# rpiz_relay.net
KiCad netlist of a schematic drawn in EAGLE
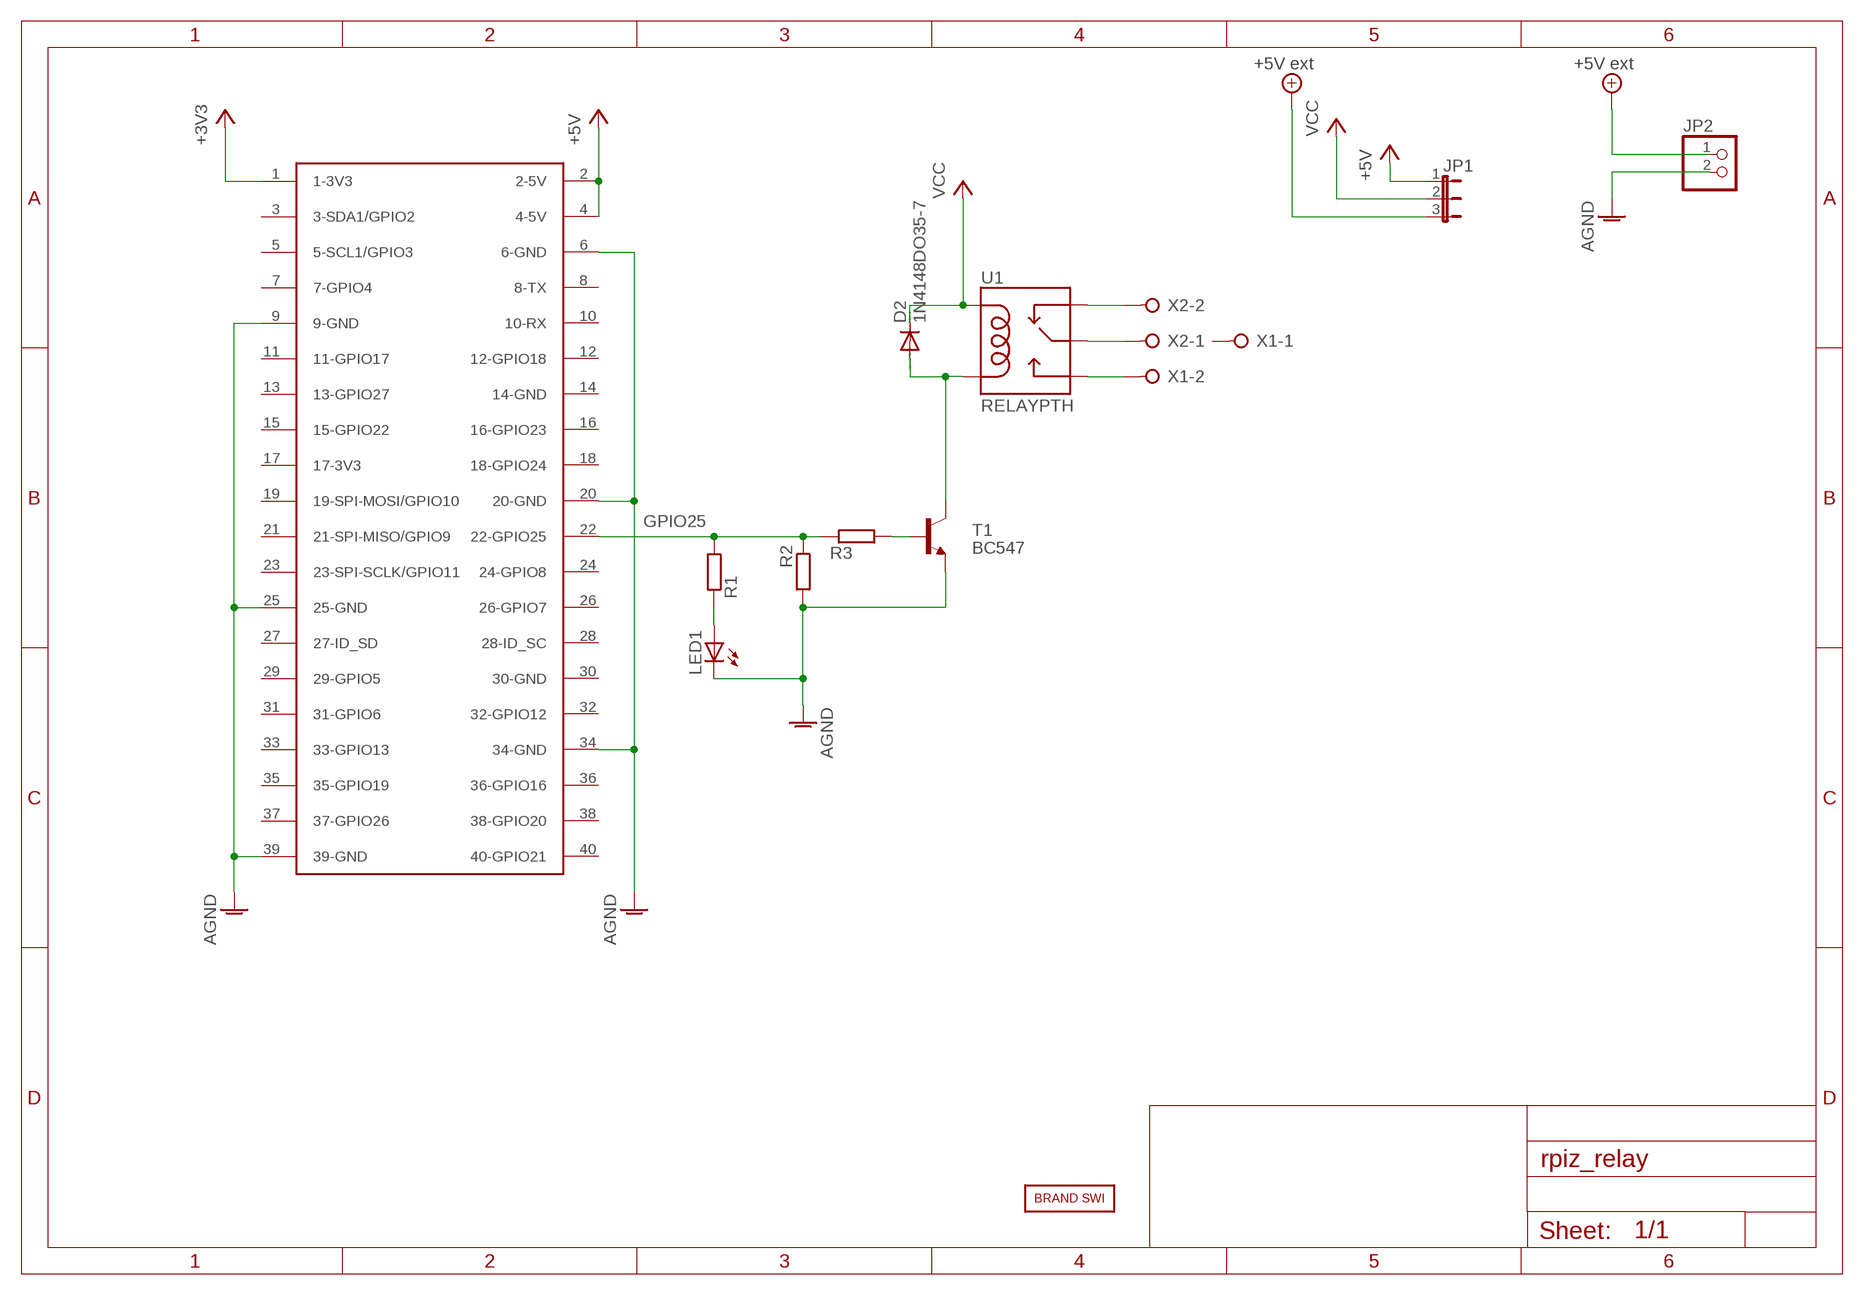
[diagram p0: schematic, sheet 1]

(export (version "E")
  (design (tool "Eeschema 10.0.6"))
  (components
    (comp (ref "D2")
      (value "1N4148DO35-7")
      (footprint "eagle-import:DO35-7")
      (libsource (lib "eagle-import") (part "1N4148DO35-7"))
    )
    (comp (ref "JP1")
      (value "JP2E")
      (footprint "eagle-import:JP2")
      (libsource (lib "eagle-import") (part "JP2E"))
    )
    (comp (ref "JP2")
      (value "PINHD-1X2")
      (footprint "eagle-import:1X02")
      (libsource (lib "eagle-import") (part "PINHD-1X2"))
    )
    (comp (ref "LED1")
      (value "LEDCHIP-LED0805")
      (footprint "eagle-import:CHIP-LED0805")
      (libsource (lib "eagle-import") (part "LEDCHIP-LED0805"))
    )
    (comp (ref "R1")
      (value "R-EU_R0805")
      (footprint "eagle-import:R0805")
      (libsource (lib "eagle-import") (part "R-EU_R0805"))
    )
    (comp (ref "R2")
      (value "R-EU_R0805")
      (footprint "eagle-import:R0805")
      (libsource (lib "eagle-import") (part "R-EU_R0805"))
    )
    (comp (ref "R3")
      (value "R-EU_R0805")
      (footprint "eagle-import:R0805")
      (libsource (lib "eagle-import") (part "R-EU_R0805"))
    )
    (comp (ref "T1")
      (value "BC547")
      (footprint "eagle-import:TO92")
      (libsource (lib "eagle-import") (part "BC547"))
    )
    (comp (ref "U$1")
      (value "RASPBERRY-PI+PIZERO")
      (footprint "eagle-import:RASPBERRY-PI-ZERO")
      (libsource (lib "eagle-import") (part "RASPBERRY-PI+PIZERO"))
    )
    (comp (ref "U$2")
      (value "BRAND_SWI5X7")
      (footprint "eagle-import:BRAND_SWI_5X7")
      (libsource (lib "eagle-import") (part "BRAND_SWI5X7"))
    )
    (comp (ref "U1")
      (value "RELAYPTH")
      (footprint "eagle-import:SRD-05VDC-SL-C")
      (libsource (lib "eagle-import") (part "RELAYPTH"))
    )
    (comp (ref "X1")
      (value "W237-02P")
      (footprint "eagle-import:W237-132")
      (libsource (lib "eagle-import") (part "W237-02P"))
    )
    (comp (ref "X2")
      (value "W237-02P")
      (footprint "eagle-import:W237-132")
      (libsource (lib "eagle-import") (part "W237-02P"))
    )
  )
  (nets
    (net (code "1") (name "+3V3") (class "Default")
      (node (ref "U$1") (pin "1") (pinfunction "1-3V3_1") (pintype "bidirectional"))
    )
    (net (code "2") (name "+5V") (class "Default")
      (node (ref "JP1") (pin "1") (pinfunction "1_1") (pintype "passive"))
      (node (ref "U$1") (pin "2") (pinfunction "2-5V_2") (pintype "bidirectional"))
      (node (ref "U$1") (pin "4") (pinfunction "4-5V_4") (pintype "bidirectional"))
    )
    (net (code "3") (name "+5V ext") (class "Default")
      (node (ref "JP1") (pin "3") (pinfunction "3_3") (pintype "passive"))
      (node (ref "JP2") (pin "1") (pinfunction "1_1") (pintype "passive"))
    )
    (net (code "4") (name "/GPIO25") (class "Default")
      (node (ref "R1") (pin "2") (pinfunction "2_2") (pintype "passive"))
      (node (ref "R2") (pin "1") (pinfunction "1_1") (pintype "passive"))
      (node (ref "R3") (pin "1") (pinfunction "1_1") (pintype "passive"))
      (node (ref "U$1") (pin "22") (pinfunction "22-GPIO25_22") (pintype "bidirectional"))
    )
    (net (code "5") (name "AGND") (class "Default")
      (node (ref "JP2") (pin "2") (pinfunction "2_2") (pintype "passive"))
      (node (ref "LED1") (pin "C") (pinfunction "C_C") (pintype "passive"))
      (node (ref "R2") (pin "2") (pinfunction "2_2") (pintype "passive"))
      (node (ref "T1") (pin "1") (pinfunction "E_1") (pintype "passive"))
      (node (ref "U$1") (pin "20") (pinfunction "20-GND_20") (pintype "bidirectional"))
      (node (ref "U$1") (pin "25") (pinfunction "25-GND_25") (pintype "bidirectional"))
      (node (ref "U$1") (pin "34") (pinfunction "34-GND_34") (pintype "bidirectional"))
      (node (ref "U$1") (pin "39") (pinfunction "39-GND_39") (pintype "bidirectional"))
      (node (ref "U$1") (pin "6") (pinfunction "6-GND_6") (pintype "bidirectional"))
      (node (ref "U$1") (pin "9") (pinfunction "9-GND_9") (pintype "bidirectional"))
    )
    (net (code "6") (name "Net-(LED1-PadA)") (class "Default")
      (node (ref "LED1") (pin "A") (pinfunction "A_A") (pintype "passive"))
      (node (ref "R1") (pin "1") (pinfunction "1_1") (pintype "passive"))
    )
    (net (code "7") (name "Net-(T1-B)") (class "Default")
      (node (ref "R3") (pin "2") (pinfunction "2_2") (pintype "passive"))
      (node (ref "T1") (pin "2") (pinfunction "B_2") (pintype "passive"))
    )
    (net (code "8") (name "Net-(T1-C)") (class "Default")
      (node (ref "D2") (pin "A") (pinfunction "A_A") (pintype "passive"))
      (node (ref "T1") (pin "3") (pinfunction "C_3") (pintype "passive"))
      (node (ref "U1") (pin "COIL0") (pinfunction "COIL0_COIL0") (pintype "bidirectional"))
    )
    (net (code "9") (name "Net-(U1-SWCLOSE)") (class "Default")
      (node (ref "U1") (pin "SWCLOSED") (pinfunction "SWCLOSE_SWCLOSED") (pintype "bidirectional"))
      (node (ref "X2") (pin "2") (pinfunction "KL_2") (pintype "passive"))
    )
    (net (code "10") (name "Net-(X1B-KL)") (class "Default")
      (node (ref "U1") (pin "SWOPEN") (pinfunction "SWOPEN_SWOPEN") (pintype "bidirectional"))
      (node (ref "X1") (pin "2") (pinfunction "KL_2") (pintype "passive"))
    )
    (net (code "11") (name "Net-(X2A-KL)") (class "Default")
      (node (ref "U1") (pin "SWCOMMON") (pinfunction "SWCOMMON_SWCOMMON") (pintype "bidirectional"))
      (node (ref "X2") (pin "1") (pinfunction "KL_1") (pintype "passive"))
    )
    (net (code "12") (name "VCC") (class "Default")
      (node (ref "D2") (pin "C") (pinfunction "C_C") (pintype "passive"))
      (node (ref "JP1") (pin "2") (pinfunction "2_2") (pintype "passive"))
      (node (ref "U1") (pin "COIL1") (pinfunction "COIL1_COIL1") (pintype "bidirectional"))
    )
    (net (code "13") (name "unconnected-(U$1-3-SDA1{slash}GPIO2-Pad3)") (class "Default")
      (node (ref "U$1") (pin "3") (pinfunction "3-SDA1/GPIO2_3") (pintype "bidirectional"))
    )
    (net (code "14") (name "unconnected-(U$1-5-SCL1{slash}GPIO3-Pad5)") (class "Default")
      (node (ref "U$1") (pin "5") (pinfunction "5-SCL1/GPIO3_5") (pintype "bidirectional"))
    )
    (net (code "15") (name "unconnected-(U$1-7-GPIO4-Pad7)") (class "Default")
      (node (ref "U$1") (pin "7") (pinfunction "7-GPIO4_7") (pintype "bidirectional"))
    )
    (net (code "16") (name "unconnected-(U$1-8-TX-Pad8)") (class "Default")
      (node (ref "U$1") (pin "8") (pinfunction "8-TX_8") (pintype "bidirectional"))
    )
    (net (code "17") (name "unconnected-(U$1-10-RX-Pad10)") (class "Default")
      (node (ref "U$1") (pin "10") (pinfunction "10-RX_10") (pintype "bidirectional"))
    )
    (net (code "18") (name "unconnected-(U$1-11-GPIO17-Pad11)") (class "Default")
      (node (ref "U$1") (pin "11") (pinfunction "11-GPIO17_11") (pintype "bidirectional"))
    )
    (net (code "19") (name "unconnected-(U$1-12-GPIO18-Pad12)") (class "Default")
      (node (ref "U$1") (pin "12") (pinfunction "12-GPIO18_12") (pintype "bidirectional"))
    )
    (net (code "20") (name "unconnected-(U$1-13-GPIO27-Pad13)") (class "Default")
      (node (ref "U$1") (pin "13") (pinfunction "13-GPIO27_13") (pintype "bidirectional"))
    )
    (net (code "21") (name "unconnected-(U$1-14-GND-Pad14)") (class "Default")
      (node (ref "U$1") (pin "14") (pinfunction "14-GND_14") (pintype "bidirectional"))
    )
    (net (code "22") (name "unconnected-(U$1-15-GPIO22-Pad15)") (class "Default")
      (node (ref "U$1") (pin "15") (pinfunction "15-GPIO22_15") (pintype "bidirectional"))
    )
    (net (code "23") (name "unconnected-(U$1-16-GPIO23-Pad16)") (class "Default")
      (node (ref "U$1") (pin "16") (pinfunction "16-GPIO23_16") (pintype "bidirectional"))
    )
    (net (code "24") (name "unconnected-(U$1-17-3V3-Pad17)") (class "Default")
      (node (ref "U$1") (pin "17") (pinfunction "17-3V3_17") (pintype "bidirectional"))
    )
    (net (code "25") (name "unconnected-(U$1-18-GPIO24-Pad18)") (class "Default")
      (node (ref "U$1") (pin "18") (pinfunction "18-GPIO24_18") (pintype "bidirectional"))
    )
    (net (code "26") (name "unconnected-(U$1-19-SPI-MOSI{slash}GPIO10-Pad19)") (class "Default")
      (node (ref "U$1") (pin "19") (pinfunction "19-SPI-MOSI/GPIO10_19") (pintype "bidirectional"))
    )
    (net (code "27") (name "unconnected-(U$1-21-SPI-MISO{slash}GPIO9-Pad21)") (class "Default")
      (node (ref "U$1") (pin "21") (pinfunction "21-SPI-MISO/GPIO9_21") (pintype "bidirectional"))
    )
    (net (code "28") (name "unconnected-(U$1-23-SPI-SCLK{slash}GPIO11-Pad23)") (class "Default")
      (node (ref "U$1") (pin "23") (pinfunction "23-SPI-SCLK/GPIO11_23") (pintype "bidirectional"))
    )
    (net (code "29") (name "unconnected-(U$1-24-GPIO8-Pad24)") (class "Default")
      (node (ref "U$1") (pin "24") (pinfunction "24-GPIO8_24") (pintype "bidirectional"))
    )
    (net (code "30") (name "unconnected-(U$1-26-GPIO7-Pad26)") (class "Default")
      (node (ref "U$1") (pin "26") (pinfunction "26-GPIO7_26") (pintype "bidirectional"))
    )
    (net (code "31") (name "unconnected-(U$1-27-ID_SD-Pad27)") (class "Default")
      (node (ref "U$1") (pin "27") (pinfunction "27-ID_SD_27") (pintype "bidirectional"))
    )
    (net (code "32") (name "unconnected-(U$1-28-ID_SC-Pad28)") (class "Default")
      (node (ref "U$1") (pin "28") (pinfunction "28-ID_SC_28") (pintype "bidirectional"))
    )
    (net (code "33") (name "unconnected-(U$1-29-GPIO5-Pad29)") (class "Default")
      (node (ref "U$1") (pin "29") (pinfunction "29-GPIO5_29") (pintype "bidirectional"))
    )
    (net (code "34") (name "unconnected-(U$1-30-GND-Pad30)") (class "Default")
      (node (ref "U$1") (pin "30") (pinfunction "30-GND_30") (pintype "bidirectional"))
    )
    (net (code "35") (name "unconnected-(U$1-31-GPIO6-Pad31)") (class "Default")
      (node (ref "U$1") (pin "31") (pinfunction "31-GPIO6_31") (pintype "bidirectional"))
    )
    (net (code "36") (name "unconnected-(U$1-32-GPIO12-Pad32)") (class "Default")
      (node (ref "U$1") (pin "32") (pinfunction "32-GPIO12_32") (pintype "bidirectional"))
    )
    (net (code "37") (name "unconnected-(U$1-33-GPIO13-Pad33)") (class "Default")
      (node (ref "U$1") (pin "33") (pinfunction "33-GPIO13_33") (pintype "bidirectional"))
    )
    (net (code "38") (name "unconnected-(U$1-35-GPIO19-Pad35)") (class "Default")
      (node (ref "U$1") (pin "35") (pinfunction "35-GPIO19_35") (pintype "bidirectional"))
    )
    (net (code "39") (name "unconnected-(U$1-36-GPIO16-Pad36)") (class "Default")
      (node (ref "U$1") (pin "36") (pinfunction "36-GPIO16_36") (pintype "bidirectional"))
    )
    (net (code "40") (name "unconnected-(U$1-37-GPIO26-Pad37)") (class "Default")
      (node (ref "U$1") (pin "37") (pinfunction "37-GPIO26_37") (pintype "bidirectional"))
    )
    (net (code "41") (name "unconnected-(U$1-38-GPIO20-Pad38)") (class "Default")
      (node (ref "U$1") (pin "38") (pinfunction "38-GPIO20_38") (pintype "bidirectional"))
    )
    (net (code "42") (name "unconnected-(U$1-40-GPIO21-Pad40)") (class "Default")
      (node (ref "U$1") (pin "40") (pinfunction "40-GPIO21_40") (pintype "bidirectional"))
    )
    (net (code "43") (name "unconnected-(X1A-KL-Pad1)") (class "Default")
      (node (ref "X1") (pin "1") (pinfunction "KL_1") (pintype "passive"))
    )
  )
)
